# 02-ChargeControl.net
KiCad netlist of a schematic drawn in Altium Designer
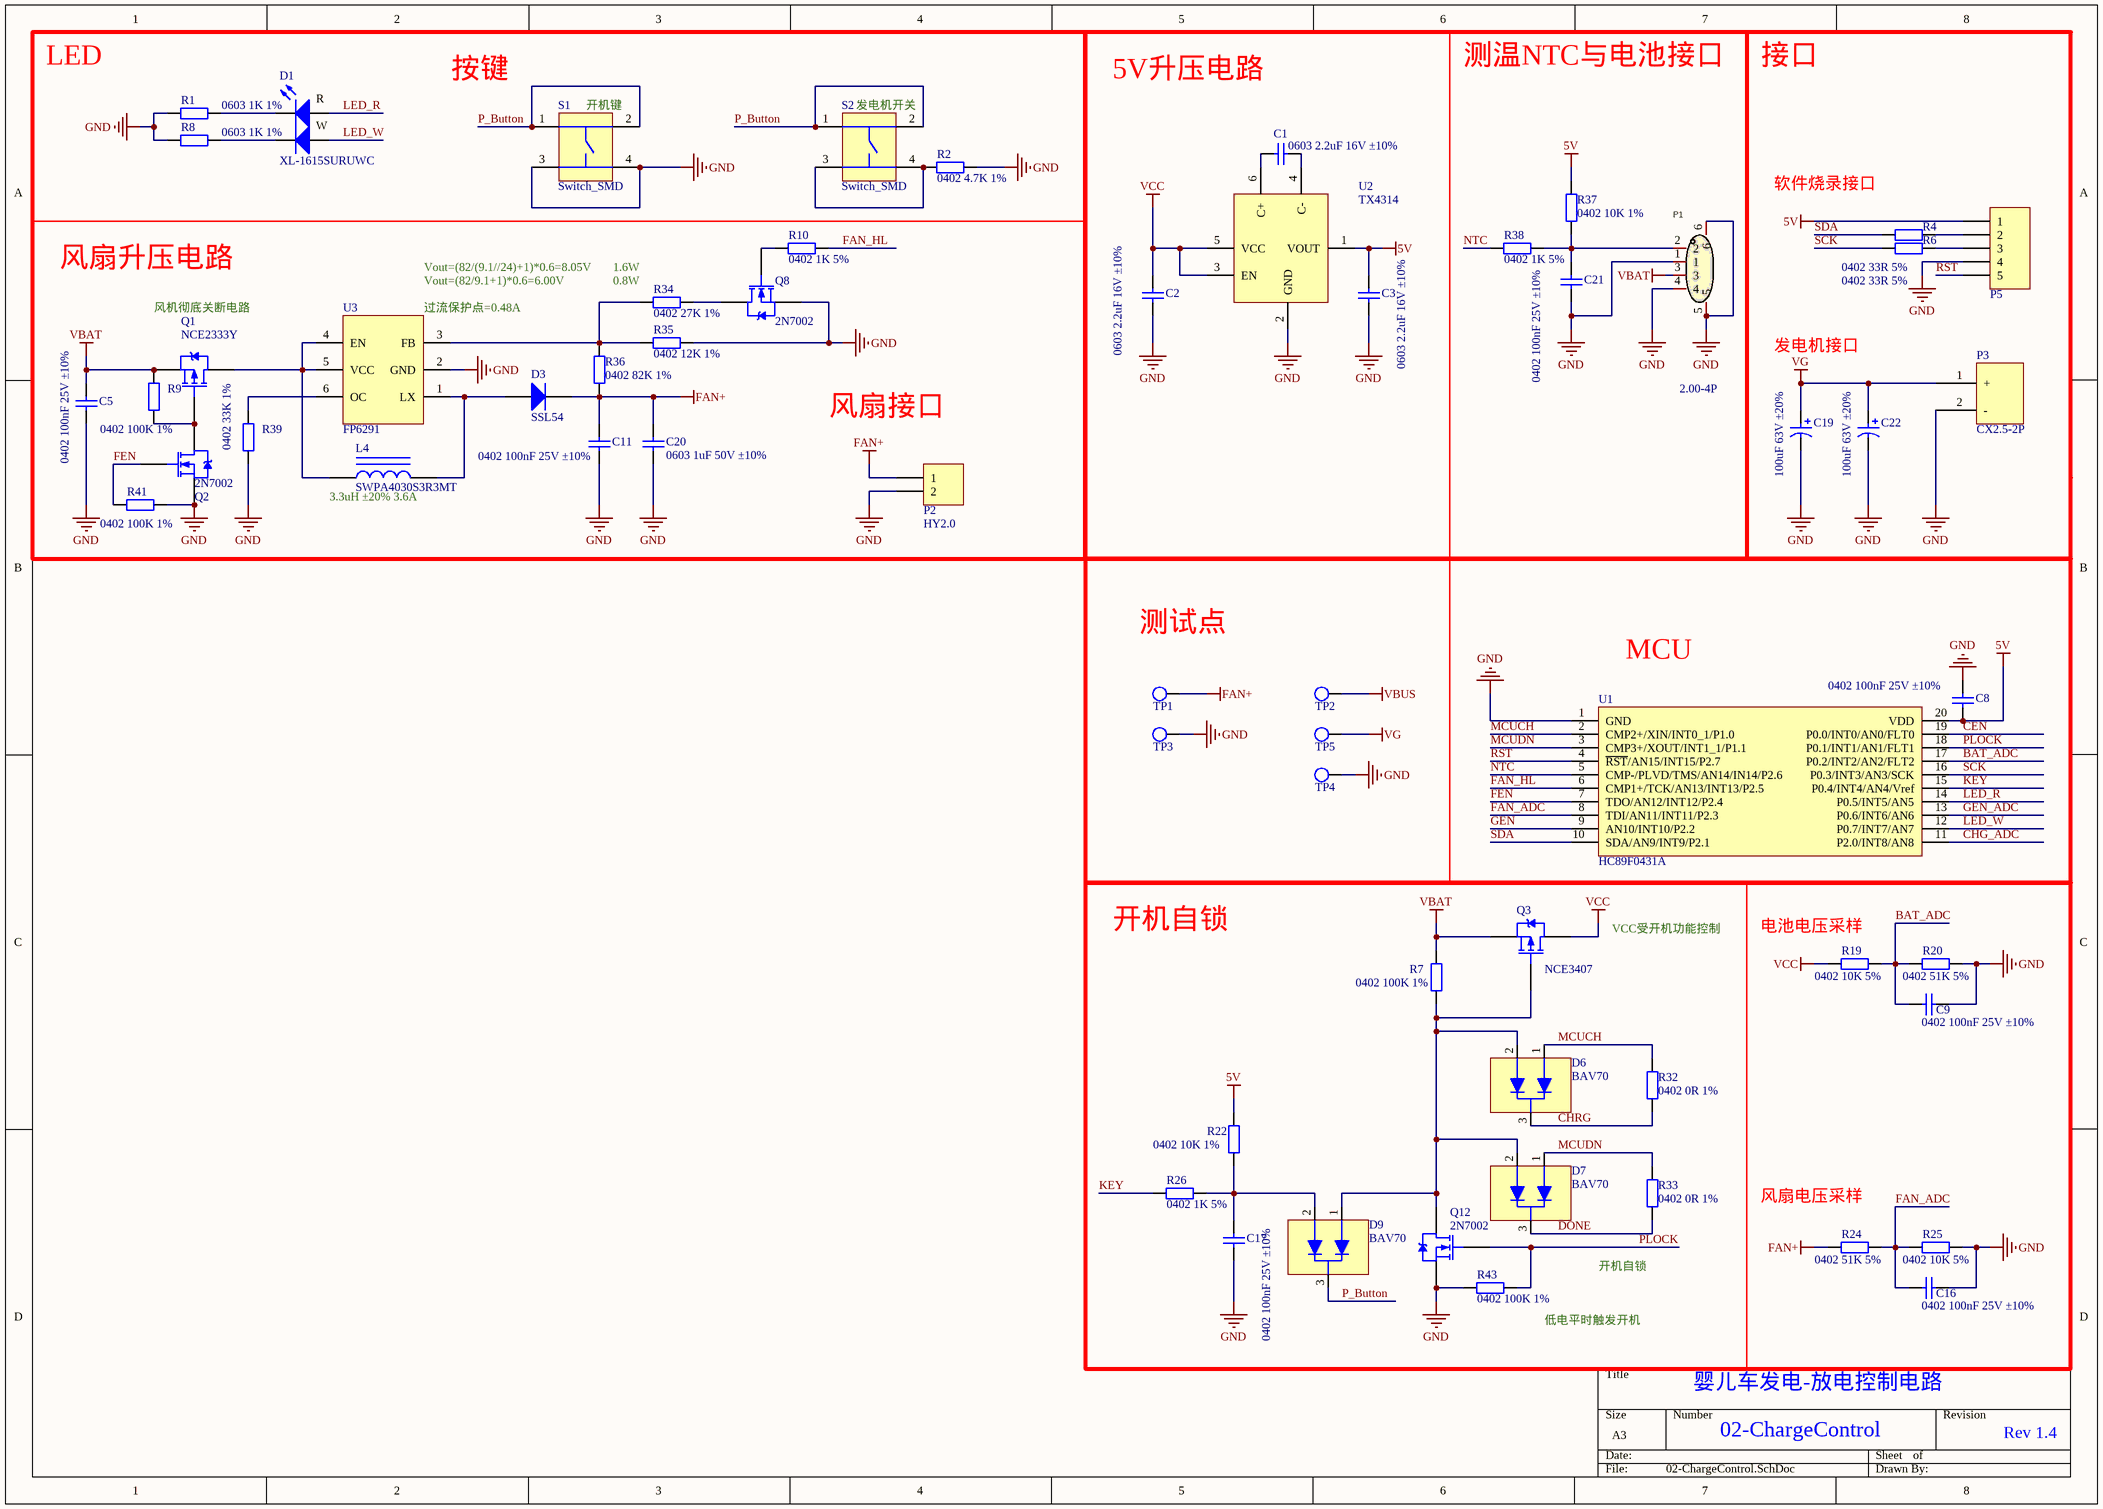
[diagram p0: 02-ChargeControl.SchDoc]

(export (version "E")
  (design (tool "Eeschema 10.0.6"))
  (components
    (comp (ref "C1")
      (value "0603 2.2uF 16V ±10%")
      (footprint "C0603")
      (description "贴片电容")
      (libsource (lib "Hoovic_Library") (part "Cap_0603"))
    )
    (comp (ref "C2")
      (value "0603 2.2uF 16V ±10%")
      (footprint "C0603")
      (description "贴片电容")
      (libsource (lib "Hoovic_Library") (part "Cap_0603"))
    )
    (comp (ref "C3")
      (value "0603 2.2uF 16V ±10%")
      (footprint "C0603")
      (description "贴片电容")
      (libsource (lib "Hoovic_Library") (part "Cap_0603"))
    )
    (comp (ref "C5")
      (value "0402 100nF 25V ±10%")
      (footprint "C0402")
      (description "贴片电容")
      (libsource (lib "Hoovic_Library") (part "Cap_0402"))
    )
    (comp (ref "C8")
      (value "0402 100nF 25V ±10%")
      (footprint "C0402")
      (description "贴片电容")
      (libsource (lib "Hoovic_Library") (part "Cap_0402"))
    )
    (comp (ref "C9")
      (value "0402 100nF 25V ±10%")
      (footprint "C0402")
      (description "贴片电容")
      (libsource (lib "Hoovic_Library") (part "Cap_0402"))
    )
    (comp (ref "C11")
      (value "0402 100nF 25V ±10%")
      (footprint "C0402")
      (description "贴片电容")
      (libsource (lib "Hoovic_Library") (part "Cap_0402"))
    )
    (comp (ref "C16")
      (value "0402 100nF 25V ±10%")
      (footprint "C0402")
      (description "贴片电容")
      (libsource (lib "Hoovic_Library") (part "Cap_0402"))
    )
    (comp (ref "C17")
      (value "0402 100nF 25V ±10%")
      (footprint "C0402")
      (description "贴片电容")
      (libsource (lib "Hoovic_Library") (part "Cap_0402"))
    )
    (comp (ref "C19")
      (value "100uF 63V ±20%")
      (footprint "CAP-TH_BD8-P3.50-D1.0-WD")
      (description "电解电容")
      (libsource (lib "Hoovic_Library") (part "Cap_elec"))
    )
    (comp (ref "C20")
      (value "0603 1uF 50V ±10%")
      (footprint "C0603")
      (description "贴片电容")
      (libsource (lib "Hoovic_Library") (part "Cap_0603"))
    )
    (comp (ref "C21")
      (value "0402 100nF 25V ±10%")
      (footprint "C0402")
      (description "贴片电容")
      (libsource (lib "Hoovic_Library") (part "Cap_0402"))
    )
    (comp (ref "C22")
      (value "100uF 63V ±20%")
      (footprint "CAP-TH_BD8-P3.50-D1.0-WD")
      (description "电解电容")
      (libsource (lib "Hoovic_Library") (part "Cap_elec"))
    )
    (comp (ref "D1")
      (value "XL-1615SURUWC")
      (footprint "LED-SMD_4P-L1.6-W1.5-RD_XL-1615SURUWC")
      (description "0603封装的红白黄色LED")
      (libsource (lib "Hoovic_Library") (part "XL-1615SURUWC"))
    )
    (comp (ref "D3")
      (value "SSL54")
      (footprint "SMB")
      (description "贴片肖特基二极管")
      (libsource (lib "Hoovic_Library") (part "SS36B"))
    )
    (comp (ref "D6")
      (value "BAV70")
      (footprint "SOT-23-3")
      (libsource (lib "80-BabyCarBatControl_SCH") (part "BAV70"))
    )
    (comp (ref "D7")
      (value "BAV70")
      (footprint "SOT-23-3")
      (libsource (lib "80-BabyCarBatControl_SCH") (part "BAV70"))
    )
    (comp (ref "D9")
      (value "BAV70")
      (footprint "SOT-23-3")
      (libsource (lib "80-BabyCarBatControl_SCH") (part "BAV70"))
    )
    (comp (ref "L4")
      (value "SWPA4030S3R3MT")
      (footprint "IND-SMD_L4.0-W4.0_SMNR4012")
      (description "功率电感")
      (libsource (lib "80-BabyCarBatControl_SCH") (part "Inductor Iron"))
    )
    (comp (ref "P1")
      (value "2.00-4P")
      (footprint "CONN-SMD_4P-P2.00")
      (description "连接器4pin，2.00间距")
      (fields (field (name "MANUFACTURER") "SHOU HAN(首韩)") (field (name "MANUFACTURER PART") "1.25-4PWTDK"))
      (libsource (lib "Hoovic_Library") (part "2.00-4PWTDK"))
    )
    (comp (ref "P2")
      (value "HY2.0")
      (footprint "CONN-SMD_HY2.0-2P")
      (description "连接器, 2-Pin")
      (libsource (lib "Hoovic_Library") (part "Header 2"))
    )
    (comp (ref "P3")
      (value "CX2.5-2P")
      (footprint "CX2.5-2P")
      (description "磁吸端子 弯插 2pin 2.5针距")
      (libsource (lib "Hoovic_Library") (part "CX2.5-2P"))
    )
    (comp (ref "P5")
      (value "Header 5")
      (footprint "CONN-TH_5P-2.54-DIR")
      (description "连接器, 5-Pin")
      (libsource (lib "Hoovic_Library") (part "Header 5"))
    )
    (comp (ref "Q1")
      (value "NCE2333Y")
      (footprint "SOT-23-3-MOSFET")
      (description "P-MOSFET with 3 Pin Vdss=60V Id=1.6A Vgs(th)=2V")
      (libsource (lib "Hoovic_Library") (part "NCE2309"))
    )
    (comp (ref "Q2")
      (value "2N7002")
      (footprint "SOT-23-3-MOSFET")
      (description "N-MOSFET with 3 Pin Vdss=60V  Id=115mA Vgs(th)=2.5V")
      (libsource (lib "Hoovic_Library") (part "2N7002"))
    )
    (comp (ref "Q3")
      (value "NCE3407")
      (footprint "SOT-23-3-MOSFET")
      (description "P-MOSFET with 3 Pin Vdss=60V Id=1.6A Vgs(th)=2V")
      (libsource (lib "Hoovic_Library") (part "NCE2309"))
    )
    (comp (ref "Q8")
      (value "2N7002")
      (footprint "SOT-23-3-MOSFET")
      (description "N-MOSFET with 3 Pin Vdss=60V  Id=115mA Vgs(th)=2.5V")
      (libsource (lib "Hoovic_Library") (part "2N7002"))
    )
    (comp (ref "Q12")
      (value "2N7002")
      (footprint "SOT-23-3-MOSFET")
      (description "N-MOSFET with 3 Pin Vdss=60V  Id=115mA Vgs(th)=2.5V")
      (libsource (lib "Hoovic_Library") (part "2N7002"))
    )
    (comp (ref "R1")
      (value "0603 1K 1%")
      (footprint "R0603")
      (description "贴片电阻")
      (libsource (lib "Hoovic_Library") (part "Res_0603"))
    )
    (comp (ref "R2")
      (value "0402 4.7K 1%")
      (footprint "R0402")
      (description "贴片电阻")
      (libsource (lib "Hoovic_Library") (part "Res_0402"))
    )
    (comp (ref "R4")
      (value "0402 33R 5%")
      (footprint "R0402")
      (description "贴片电阻")
      (libsource (lib "Hoovic_Library") (part "Res_0402"))
    )
    (comp (ref "R6")
      (value "0402 33R 5%")
      (footprint "R0402")
      (description "贴片电阻")
      (libsource (lib "Hoovic_Library") (part "Res_0402"))
    )
    (comp (ref "R7")
      (value "0402 100K 1%")
      (footprint "R0402")
      (description "贴片电阻")
      (libsource (lib "") (part "Res_0402_2"))
    )
    (comp (ref "R8")
      (value "0603 1K 1%")
      (footprint "R0603")
      (description "贴片电阻")
      (libsource (lib "Hoovic_Library") (part "Res_0603"))
    )
    (comp (ref "R9")
      (value "0402 100K 1%")
      (footprint "R0402")
      (description "贴片电阻")
      (libsource (lib "") (part "Res_0402_2"))
    )
    (comp (ref "R10")
      (value "0402 1K 5%")
      (footprint "R0402")
      (description "贴片电阻")
      (libsource (lib "") (part "Res_0402_3"))
    )
    (comp (ref "R19")
      (value "0402 10K 5%")
      (footprint "R0402")
      (description "贴片电阻")
      (libsource (lib "Hoovic_Library") (part "Res_0402"))
    )
    (comp (ref "R20")
      (value "0402 51K 5%")
      (footprint "R0402")
      (description "贴片电阻")
      (libsource (lib "Hoovic_Library") (part "Res_0402"))
    )
    (comp (ref "R22")
      (value "0402 10K 1%")
      (footprint "R0402")
      (description "贴片电阻")
      (libsource (lib "") (part "Res_0402_2"))
    )
    (comp (ref "R24")
      (value "0402 51K 5%")
      (footprint "R0402")
      (description "贴片电阻")
      (libsource (lib "Hoovic_Library") (part "Res_0402"))
    )
    (comp (ref "R25")
      (value "0402 10K 5%")
      (footprint "R0402")
      (description "贴片电阻")
      (libsource (lib "Hoovic_Library") (part "Res_0402"))
    )
    (comp (ref "R26")
      (value "0402 1K 5%")
      (footprint "R0402")
      (description "贴片电阻")
      (libsource (lib "") (part "Res_0402_3"))
    )
    (comp (ref "R32")
      (value "0402 0R 1%")
      (footprint "R0402")
      (description "贴片电阻")
      (libsource (lib "") (part "Res_0402_1"))
    )
    (comp (ref "R33")
      (value "0402 0R 1%")
      (footprint "R0402")
      (description "贴片电阻")
      (libsource (lib "") (part "Res_0402_1"))
    )
    (comp (ref "R34")
      (value "0402 27K 1%")
      (footprint "R0402")
      (description "贴片电阻")
      (libsource (lib "") (part "Res_0402_3"))
    )
    (comp (ref "R35")
      (value "0402 12K 1%")
      (footprint "R0402")
      (description "贴片电阻")
      (libsource (lib "") (part "Res_0402_3"))
    )
    (comp (ref "R36")
      (value "0402 82K 1%")
      (footprint "R0402")
      (description "贴片电阻")
      (libsource (lib "") (part "Res_0402_1"))
    )
    (comp (ref "R37")
      (value "0402 10K 1%")
      (footprint "R0402")
      (description "贴片电阻")
      (libsource (lib "") (part "Res_0402_1"))
    )
    (comp (ref "R38")
      (value "0402 1K 5%")
      (footprint "R0402")
      (description "贴片电阻")
      (libsource (lib "") (part "Res_0402_4"))
    )
    (comp (ref "R39")
      (value "0402 33K 1%")
      (footprint "R0402")
      (description "贴片电阻")
      (libsource (lib "") (part "Res_0402_2"))
    )
    (comp (ref "R41")
      (value "0402 100K 1%")
      (footprint "R0402")
      (description "贴片电阻")
      (libsource (lib "Hoovic_Library") (part "Res_0402"))
    )
    (comp (ref "R43")
      (value "0402 100K 1%")
      (footprint "R0402")
      (description "贴片电阻")
      (libsource (lib "") (part "Res_0402_3"))
    )
    (comp (ref "S1")
      (value "Switch_SMD")
      (footprint "SMD-4_6x6")
      (description "4PIN按键开关")
      (libsource (lib "Hoovic_Library") (part "Switch_SMD_4P"))
    )
    (comp (ref "S2")
      (value "Switch_SMD")
      (footprint "SMD-4_6x6")
      (description "4PIN按键开关")
      (libsource (lib "Hoovic_Library") (part "Switch_SMD_4P"))
    )
    (comp (ref "TP1")
      (value "TestPoint")
      (footprint "TESTPOINT-70MIL")
      (description "测试点")
      (libsource (lib "Hoovic_Library") (part "TP"))
    )
    (comp (ref "TP2")
      (value "TestPoint")
      (footprint "TESTPOINT-70MIL")
      (description "测试点")
      (libsource (lib "Hoovic_Library") (part "TP"))
    )
    (comp (ref "TP3")
      (value "TestPoint")
      (footprint "TESTPOINT-70MIL")
      (description "测试点")
      (libsource (lib "Hoovic_Library") (part "TP"))
    )
    (comp (ref "TP4")
      (value "TestPoint")
      (footprint "TESTPOINT-70MIL")
      (description "测试点")
      (libsource (lib "Hoovic_Library") (part "TP"))
    )
    (comp (ref "TP5")
      (value "TestPoint")
      (footprint "TESTPOINT-70MIL")
      (description "测试点")
      (libsource (lib "Hoovic_Library") (part "TP"))
    )
    (comp (ref "U1")
      (value "HC89F0431A")
      (footprint "TSSOP-20")
      (description "芯圣HC89F0431A")
      (libsource (lib "Hoovic_Library") (part "HC89F0431A"))
    )
    (comp (ref "U2")
      (value "TX4314")
      (footprint "SOT-23-6")
      (description "DC-DC升压电荷泵")
      (libsource (lib "80-BabyCarBatControl_SCH") (part "TX4314"))
    )
    (comp (ref "U3")
      (value "FP6291")
      (footprint "SOT-23-6")
      (description "DC-DC升压控制芯片")
      (libsource (lib "80-BabyCarBatControl_SCH") (part "FP6291"))
    )
  )
  (nets
    (net (code "1") (name "/BAT_ADC") (class "Default")
      (node (ref "C9") (pin "2") (pinfunction "2_2") (pintype "passive"))
      (node (ref "R19") (pin "2") (pinfunction "2_2") (pintype "passive"))
      (node (ref "R20") (pin "1") (pinfunction "1_1") (pintype "passive"))
      (node (ref "U1") (pin "17") (pinfunction "P0.2/INT2/AN2/FLT2_17") (pintype "passive"))
    )
    (net (code "2") (name "/CEN") (class "Default")
      (node (ref "U1") (pin "19") (pinfunction "P0.0/INT0/AN0/FLT0_19") (pintype "passive"))
    )
    (net (code "3") (name "/CHG_ADC") (class "Default")
      (node (ref "U1") (pin "11") (pinfunction "P2.0/INT8/AN8_11") (pintype "passive"))
    )
    (net (code "4") (name "/CHRG") (class "Default")
      (node (ref "D6") (pin "3") (pinfunction "K_3") (pintype "passive"))
      (node (ref "R32") (pin "1") (pinfunction "1_1") (pintype "passive"))
    )
    (net (code "5") (name "/DONE") (class "Default")
      (node (ref "D7") (pin "3") (pinfunction "K_3") (pintype "passive"))
      (node (ref "R33") (pin "1") (pinfunction "1_1") (pintype "passive"))
    )
    (net (code "6") (name "/FAN_ADC") (class "Default")
      (node (ref "C16") (pin "2") (pinfunction "2_2") (pintype "passive"))
      (node (ref "R24") (pin "2") (pinfunction "2_2") (pintype "passive"))
      (node (ref "R25") (pin "1") (pinfunction "1_1") (pintype "passive"))
      (node (ref "U1") (pin "8") (pinfunction "TDI/AN11/INT11/P2.3_8") (pintype "passive"))
    )
    (net (code "7") (name "/FAN_HL") (class "Default")
      (node (ref "R10") (pin "1") (pinfunction "1_1") (pintype "passive"))
      (node (ref "U1") (pin "6") (pinfunction "CMP1+/TCK/AN13/INT13/P2.5_6") (pintype "passive"))
    )
    (net (code "8") (name "/FEN") (class "Default")
      (node (ref "Q2") (pin "1") (pinfunction "G_1") (pintype "passive"))
      (node (ref "R41") (pin "1") (pinfunction "1_1") (pintype "passive"))
      (node (ref "U1") (pin "7") (pinfunction "TDO/AN12/INT12/P2.4_7") (pintype "passive"))
    )
    (net (code "9") (name "/GEN") (class "Default")
      (node (ref "U1") (pin "9") (pinfunction "AN10/INT10/P2.2_9") (pintype "passive"))
    )
    (net (code "10") (name "/GEN_ADC") (class "Default")
      (node (ref "U1") (pin "13") (pinfunction "P0.6/INT6/AN6_13") (pintype "passive"))
    )
    (net (code "11") (name "/KEY") (class "Default")
      (node (ref "R26") (pin "2") (pinfunction "2_2") (pintype "passive"))
      (node (ref "U1") (pin "15") (pinfunction "P0.4/INT4/AN4/Vref_15") (pintype "passive"))
    )
    (net (code "12") (name "/LED_R") (class "Default")
      (node (ref "D1") (pin "2") (pinfunction "+_2") (pintype "passive"))
      (node (ref "U1") (pin "14") (pinfunction "P0.5/INT5/AN5_14") (pintype "passive"))
    )
    (net (code "13") (name "/LED_W") (class "Default")
      (node (ref "D1") (pin "4") (pinfunction "+_4") (pintype "passive"))
      (node (ref "U1") (pin "12") (pinfunction "P0.7/INT7/AN7_12") (pintype "passive"))
    )
    (net (code "14") (name "/MCUCH") (class "Default")
      (node (ref "D6") (pin "1") (pinfunction "A1_1") (pintype "passive"))
      (node (ref "R32") (pin "2") (pinfunction "2_2") (pintype "passive"))
      (node (ref "U1") (pin "2") (pinfunction "CMP2+/XIN/INT0_1/P1.0_2") (pintype "passive"))
    )
    (net (code "15") (name "/MCUDN") (class "Default")
      (node (ref "D7") (pin "1") (pinfunction "A1_1") (pintype "passive"))
      (node (ref "R33") (pin "2") (pinfunction "2_2") (pintype "passive"))
      (node (ref "U1") (pin "3") (pinfunction "CMP3+/XOUT/INT1_1/P1.1_3") (pintype "passive"))
    )
    (net (code "16") (name "/NTC") (class "Default")
      (node (ref "R38") (pin "1") (pinfunction "1_1") (pintype "passive"))
      (node (ref "U1") (pin "5") (pinfunction "CMP-/PLVD/TMS/AN14/IN14/P2.6_5") (pintype "passive"))
    )
    (net (code "17") (name "/PLOCK") (class "Default")
      (node (ref "Q12") (pin "1") (pinfunction "G_1") (pintype "passive"))
      (node (ref "R43") (pin "1") (pinfunction "1_1") (pintype "passive"))
      (node (ref "U1") (pin "18") (pinfunction "P0.1/INT1/AN1/FLT1_18") (pintype "passive"))
    )
    (net (code "18") (name "/P_Button") (class "Default")
      (node (ref "D9") (pin "3") (pinfunction "K_3") (pintype "passive"))
      (node (ref "S1") (pin "1") (pinfunction "1_1") (pintype "passive"))
      (node (ref "S1") (pin "2") (pinfunction "2_2") (pintype "passive"))
      (node (ref "S2") (pin "1") (pinfunction "1_1") (pintype "passive"))
      (node (ref "S2") (pin "2") (pinfunction "2_2") (pintype "passive"))
    )
    (net (code "19") (name "/RST") (class "Default")
      (node (ref "P5") (pin "5") (pinfunction "5_5") (pintype "passive"))
      (node (ref "U1") (pin "4") (pinfunction "~{RST}/AN15/INT15/P2.7_4") (pintype "passive"))
    )
    (net (code "20") (name "/SCK") (class "Default")
      (node (ref "R6") (pin "1") (pinfunction "1_1") (pintype "passive"))
      (node (ref "U1") (pin "16") (pinfunction "P0.3/INT3/AN3/SCK_16") (pintype "passive"))
    )
    (net (code "21") (name "/SDA") (class "Default")
      (node (ref "R4") (pin "1") (pinfunction "1_1") (pintype "passive"))
      (node (ref "U1") (pin "10") (pinfunction "SDA/AN9/INT9/P2.1_10") (pintype "passive"))
    )
    (net (code "22") (name "5V") (class "Default")
      (node (ref "C3") (pin "2") (pinfunction "2_2") (pintype "passive"))
      (node (ref "C8") (pin "1") (pinfunction "1_1") (pintype "passive"))
      (node (ref "P5") (pin "1") (pinfunction "1_1") (pintype "passive"))
      (node (ref "R22") (pin "1") (pinfunction "1_1") (pintype "passive"))
      (node (ref "R37") (pin "2") (pinfunction "2_2") (pintype "passive"))
      (node (ref "U1") (pin "20") (pinfunction "VDD_20") (pintype "passive"))
      (node (ref "U2") (pin "1") (pinfunction "VOUT_1") (pintype "passive"))
    )
    (net (code "23") (name "FAN+") (class "Default")
      (node (ref "C11") (pin "2") (pinfunction "2_2") (pintype "passive"))
      (node (ref "C20") (pin "2") (pinfunction "2_2") (pintype "passive"))
      (node (ref "D3") (pin "1") (pinfunction "K_1") (pintype "passive"))
      (node (ref "P2") (pin "1") (pinfunction "1_1") (pintype "passive"))
      (node (ref "R24") (pin "1") (pinfunction "1_1") (pintype "passive"))
      (node (ref "R36") (pin "1") (pinfunction "1_1") (pintype "passive"))
      (node (ref "TP1") (pin "1") (pinfunction "1_1") (pintype "passive"))
    )
    (net (code "24") (name "GND") (class "Default")
      (node (ref "C11") (pin "1") (pinfunction "1_1") (pintype "passive"))
      (node (ref "C16") (pin "1") (pinfunction "1_1") (pintype "passive"))
      (node (ref "C17") (pin "1") (pinfunction "1_1") (pintype "passive"))
      (node (ref "C19") (pin "2") (pinfunction "2_2") (pintype "passive"))
      (node (ref "C2") (pin "1") (pinfunction "1_1") (pintype "passive"))
      (node (ref "C20") (pin "1") (pinfunction "1_1") (pintype "passive"))
      (node (ref "C21") (pin "1") (pinfunction "1_1") (pintype "passive"))
      (node (ref "C22") (pin "2") (pinfunction "2_2") (pintype "passive"))
      (node (ref "C3") (pin "1") (pinfunction "1_1") (pintype "passive"))
      (node (ref "C5") (pin "1") (pinfunction "1_1") (pintype "passive"))
      (node (ref "C8") (pin "2") (pinfunction "2_2") (pintype "passive"))
      (node (ref "C9") (pin "1") (pinfunction "1_1") (pintype "passive"))
      (node (ref "P1") (pin "1") (pinfunction "1_1") (pintype "passive"))
      (node (ref "P1") (pin "4") (pinfunction "4_4") (pintype "passive"))
      (node (ref "P1") (pin "5") (pinfunction "5_5") (pintype "passive"))
      (node (ref "P1") (pin "6") (pinfunction "6_6") (pintype "passive"))
      (node (ref "P2") (pin "2") (pinfunction "2_2") (pintype "passive"))
      (node (ref "P3") (pin "2") (pinfunction "-_2") (pintype "passive"))
      (node (ref "P5") (pin "4") (pinfunction "4_4") (pintype "passive"))
      (node (ref "Q12") (pin "3") (pinfunction "S_3") (pintype "passive"))
      (node (ref "Q2") (pin "3") (pinfunction "S_3") (pintype "passive"))
      (node (ref "Q8") (pin "3") (pinfunction "S_3") (pintype "passive"))
      (node (ref "R1") (pin "2") (pinfunction "2_2") (pintype "passive"))
      (node (ref "R2") (pin "2") (pinfunction "2_2") (pintype "passive"))
      (node (ref "R20") (pin "2") (pinfunction "2_2") (pintype "passive"))
      (node (ref "R25") (pin "2") (pinfunction "2_2") (pintype "passive"))
      (node (ref "R35") (pin "1") (pinfunction "1_1") (pintype "passive"))
      (node (ref "R39") (pin "2") (pinfunction "2_2") (pintype "passive"))
      (node (ref "R41") (pin "2") (pinfunction "2_2") (pintype "passive"))
      (node (ref "R43") (pin "2") (pinfunction "2_2") (pintype "passive"))
      (node (ref "R8") (pin "2") (pinfunction "2_2") (pintype "passive"))
      (node (ref "S1") (pin "3") (pinfunction "3_3") (pintype "passive"))
      (node (ref "S1") (pin "4") (pinfunction "4_4") (pintype "passive"))
      (node (ref "TP3") (pin "1") (pinfunction "1_1") (pintype "passive"))
      (node (ref "TP4") (pin "1") (pinfunction "1_1") (pintype "passive"))
      (node (ref "U1") (pin "1") (pinfunction "GND_1") (pintype "passive"))
      (node (ref "U2") (pin "2") (pinfunction "GND_2") (pintype "passive"))
      (node (ref "U3") (pin "2") (pinfunction "GND_2") (pintype "passive"))
    )
    (net (code "25") (name "Net-(C21-Pad2)") (class "Default")
      (node (ref "C21") (pin "2") (pinfunction "2_2") (pintype "passive"))
      (node (ref "P1") (pin "2") (pinfunction "2_2") (pintype "passive"))
      (node (ref "R37") (pin "1") (pinfunction "1_1") (pintype "passive"))
      (node (ref "R38") (pin "2") (pinfunction "2_2") (pintype "passive"))
    )
    (net (code "26") (name "Net-(D1---Pad1)") (class "Default")
      (node (ref "D1") (pin "1") (pinfunction "-_1") (pintype "passive"))
      (node (ref "R1") (pin "1") (pinfunction "1_1") (pintype "passive"))
    )
    (net (code "27") (name "Net-(D1---Pad3)") (class "Default")
      (node (ref "D1") (pin "3") (pinfunction "-_3") (pintype "passive"))
      (node (ref "R8") (pin "1") (pinfunction "1_1") (pintype "passive"))
    )
    (net (code "28") (name "Net-(D3-A)") (class "Default")
      (node (ref "D3") (pin "2") (pinfunction "A_2") (pintype "passive"))
      (node (ref "L4") (pin "2") (pinfunction "2_2") (pintype "passive"))
      (node (ref "U3") (pin "1") (pinfunction "LX_1") (pintype "passive"))
    )
    (net (code "29") (name "Net-(D6-A2)") (class "Default")
      (node (ref "D6") (pin "2") (pinfunction "A2_2") (pintype "passive"))
      (node (ref "D7") (pin "2") (pinfunction "A2_2") (pintype "passive"))
      (node (ref "D9") (pin "1") (pinfunction "A1_1") (pintype "passive"))
      (node (ref "Q12") (pin "2") (pinfunction "D_2") (pintype "passive"))
      (node (ref "Q3") (pin "1") (pinfunction "G_1") (pintype "passive"))
      (node (ref "R7") (pin "2") (pinfunction "2_2") (pintype "passive"))
    )
    (net (code "30") (name "Net-(D9-A2)") (class "Default")
      (node (ref "C17") (pin "2") (pinfunction "2_2") (pintype "passive"))
      (node (ref "D9") (pin "2") (pinfunction "A2_2") (pintype "passive"))
      (node (ref "R22") (pin "2") (pinfunction "2_2") (pintype "passive"))
      (node (ref "R26") (pin "1") (pinfunction "1_1") (pintype "passive"))
    )
    (net (code "31") (name "Net-(P5-Pad2)") (class "Default")
      (node (ref "P5") (pin "2") (pinfunction "2_2") (pintype "passive"))
      (node (ref "R4") (pin "2") (pinfunction "2_2") (pintype "passive"))
    )
    (net (code "32") (name "Net-(P5-Pad3)") (class "Default")
      (node (ref "P5") (pin "3") (pinfunction "3_3") (pintype "passive"))
      (node (ref "R6") (pin "2") (pinfunction "2_2") (pintype "passive"))
    )
    (net (code "33") (name "Net-(Q1-D)") (class "Default")
      (node (ref "L4") (pin "1") (pinfunction "1_1") (pintype "passive"))
      (node (ref "Q1") (pin "2") (pinfunction "D_2") (pintype "passive"))
      (node (ref "U3") (pin "4") (pinfunction "EN_4") (pintype "passive"))
      (node (ref "U3") (pin "5") (pinfunction "VCC_5") (pintype "passive"))
    )
    (net (code "34") (name "Net-(Q1-G)") (class "Default")
      (node (ref "Q1") (pin "1") (pinfunction "G_1") (pintype "passive"))
      (node (ref "Q2") (pin "2") (pinfunction "D_2") (pintype "passive"))
      (node (ref "R9") (pin "2") (pinfunction "2_2") (pintype "passive"))
    )
    (net (code "35") (name "Net-(Q8-D)") (class "Default")
      (node (ref "Q8") (pin "2") (pinfunction "D_2") (pintype "passive"))
      (node (ref "R34") (pin "1") (pinfunction "1_1") (pintype "passive"))
    )
    (net (code "36") (name "Net-(Q8-G)") (class "Default")
      (node (ref "Q8") (pin "1") (pinfunction "G_1") (pintype "passive"))
      (node (ref "R10") (pin "2") (pinfunction "2_2") (pintype "passive"))
    )
    (net (code "37") (name "Net-(R2-Pad1)") (class "Default")
      (node (ref "R2") (pin "1") (pinfunction "1_1") (pintype "passive"))
      (node (ref "S2") (pin "3") (pinfunction "3_3") (pintype "passive"))
      (node (ref "S2") (pin "4") (pinfunction "4_4") (pintype "passive"))
    )
    (net (code "38") (name "Net-(U2-C+)") (class "Default")
      (node (ref "C1") (pin "2") (pinfunction "2_2") (pintype "passive"))
      (node (ref "U2") (pin "6") (pinfunction "C+_6") (pintype "passive"))
    )
    (net (code "39") (name "Net-(U2-C-)") (class "Default")
      (node (ref "C1") (pin "1") (pinfunction "1_1") (pintype "passive"))
      (node (ref "U2") (pin "4") (pinfunction "C-_4") (pintype "passive"))
    )
    (net (code "40") (name "Net-(U3-FB)") (class "Default")
      (node (ref "R34") (pin "2") (pinfunction "2_2") (pintype "passive"))
      (node (ref "R35") (pin "2") (pinfunction "2_2") (pintype "passive"))
      (node (ref "R36") (pin "2") (pinfunction "2_2") (pintype "passive"))
      (node (ref "U3") (pin "3") (pinfunction "FB_3") (pintype "passive"))
    )
    (net (code "41") (name "Net-(U3-OC)") (class "Default")
      (node (ref "R39") (pin "1") (pinfunction "1_1") (pintype "passive"))
      (node (ref "U3") (pin "6") (pinfunction "OC_6") (pintype "passive"))
    )
    (net (code "42") (name "VBAT") (class "Default")
      (node (ref "C5") (pin "2") (pinfunction "2_2") (pintype "passive"))
      (node (ref "P1") (pin "3") (pinfunction "3_3") (pintype "passive"))
      (node (ref "Q1") (pin "3") (pinfunction "S_3") (pintype "passive"))
      (node (ref "Q3") (pin "3") (pinfunction "S_3") (pintype "passive"))
      (node (ref "R7") (pin "1") (pinfunction "1_1") (pintype "passive"))
      (node (ref "R9") (pin "1") (pinfunction "1_1") (pintype "passive"))
    )
    (net (code "43") (name "VBUS") (class "Default")
      (node (ref "TP2") (pin "1") (pinfunction "1_1") (pintype "passive"))
    )
    (net (code "44") (name "VCC") (class "Default")
      (node (ref "C2") (pin "2") (pinfunction "2_2") (pintype "passive"))
      (node (ref "Q3") (pin "2") (pinfunction "D_2") (pintype "passive"))
      (node (ref "R19") (pin "1") (pinfunction "1_1") (pintype "passive"))
      (node (ref "U2") (pin "3") (pinfunction "EN_3") (pintype "passive"))
      (node (ref "U2") (pin "5") (pinfunction "VCC_5") (pintype "passive"))
    )
    (net (code "45") (name "VG") (class "Default")
      (node (ref "C19") (pin "1") (pinfunction "1_1") (pintype "passive"))
      (node (ref "C22") (pin "1") (pinfunction "1_1") (pintype "passive"))
      (node (ref "P3") (pin "1") (pinfunction "+_1") (pintype "passive"))
      (node (ref "TP5") (pin "1") (pinfunction "1_1") (pintype "passive"))
    )
  )
)
